# motor_control.net
KiCad netlist of a schematic drawn in EAGLE
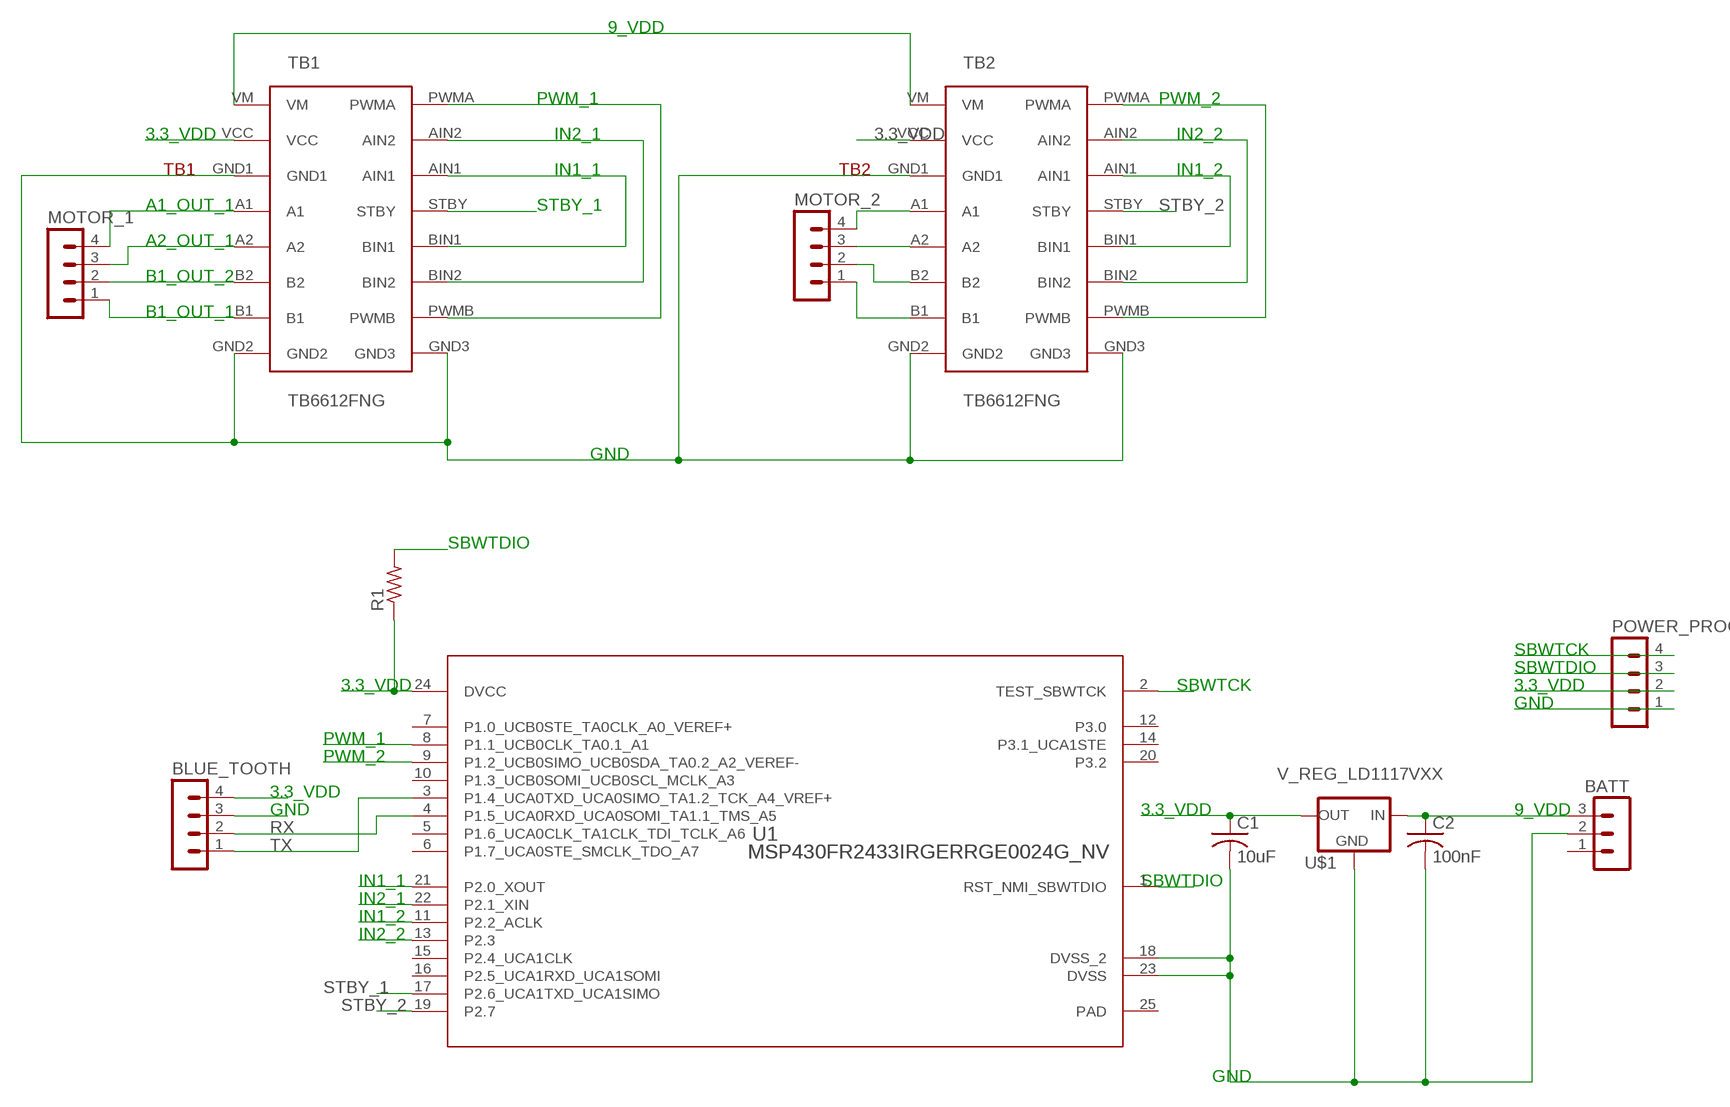
[diagram p0: schematic, sheet 1]

(export (version "E")
  (design (tool "Eeschema 10.0.6"))
  (components
    (comp (ref "BATT")
      (value "MA03-1")
      (footprint "eagle-import:MA03-1")
      (libsource (lib "eagle-import") (part "MA03-1"))
    )
    (comp (ref "BLUE_TOOTH")
      (value "MA04-1")
      (footprint "eagle-import:MA04-1")
      (libsource (lib "eagle-import") (part "MA04-1"))
    )
    (comp (ref "C1")
      (value "10uF")
      (footprint "eagle-import:C1206")
      (libsource (lib "eagle-import") (part "C-USC1206"))
    )
    (comp (ref "C2")
      (value "100nF")
      (footprint "eagle-import:C1206")
      (libsource (lib "eagle-import") (part "C-USC1206"))
    )
    (comp (ref "MOTOR_1")
      (value "MA04-1")
      (footprint "eagle-import:MA04-1")
      (libsource (lib "eagle-import") (part "MA04-1"))
    )
    (comp (ref "MOTOR_2")
      (value "MA04-1")
      (footprint "eagle-import:MA04-1")
      (libsource (lib "eagle-import") (part "MA04-1"))
    )
    (comp (ref "POWER_PROG")
      (value "MA04-1")
      (footprint "eagle-import:MA04-1")
      (libsource (lib "eagle-import") (part "MA04-1"))
    )
    (comp (ref "R1")
      (value "R-US_R1206")
      (footprint "eagle-import:R1206")
      (libsource (lib "eagle-import") (part "R-US_R1206"))
    )
    (comp (ref "TB1")
      (value "TB6612FNG")
      (footprint "eagle-import:TB6612FNG")
      (libsource (lib "eagle-import") (part "TB6612FNG"))
    )
    (comp (ref "TB2")
      (value "TB6612FNG")
      (footprint "eagle-import:TB6612FNG")
      (libsource (lib "eagle-import") (part "TB6612FNG"))
    )
    (comp (ref "U$1")
      (value "V_REG_LD1117VXX")
      (footprint "eagle-import:78XXL")
      (libsource (lib "eagle-import") (part "V_REG_LD1117VXX"))
    )
    (comp (ref "U1")
      (value "MSP430FR2433IRGERRGE0024G_NV")
      (footprint "eagle-import:RGE0024G_NV")
      (fields
        (field (name "MANUFACTURER_PART_NUMBER") "MSP430FR2433IRGER")
        (field (name "COPYRIGHT") "Copyright (C) 2023 Ultra Librarian. All rights reserved.")
      )
      (libsource (lib "eagle-import") (part "MSP430FR2433IRGERRGE0024G_NV"))
    )
  )
  (nets
    (net (code "1") (name "/3.3_VDD") (class "Default")
      (node (ref "BLUE_TOOTH") (pin "4") (pinfunction "4_4") (pintype "passive"))
      (node (ref "C1") (pin "1") (pinfunction "1_1") (pintype "passive"))
      (node (ref "POWER_PROG") (pin "2") (pinfunction "2_2") (pintype "passive"))
      (node (ref "R1") (pin "1") (pinfunction "1_1") (pintype "passive"))
      (node (ref "TB1") (pin "VCC") (pinfunction "VCC_VCC") (pintype "bidirectional"))
      (node (ref "TB2") (pin "VCC") (pinfunction "VCC_VCC") (pintype "bidirectional"))
      (node (ref "U$1") (pin "GND") (pinfunction "OUT_GND") (pintype "output"))
      (node (ref "U1") (pin "24") (pinfunction "DVCC_24") (pintype "power_in"))
    )
    (net (code "2") (name "/9_VDD") (class "Default")
      (node (ref "BATT") (pin "3") (pinfunction "3_3") (pintype "passive"))
      (node (ref "C2") (pin "1") (pinfunction "1_1") (pintype "passive"))
      (node (ref "TB1") (pin "VM") (pinfunction "VM_VM") (pintype "bidirectional"))
      (node (ref "TB2") (pin "VM") (pinfunction "VM_VM") (pintype "bidirectional"))
      (node (ref "U$1") (pin "OUT") (pinfunction "IN_OUT") (pintype "input"))
    )
    (net (code "3") (name "/A1_OUT_1") (class "Default")
      (node (ref "MOTOR_1") (pin "4") (pinfunction "4_4") (pintype "passive"))
      (node (ref "TB1") (pin "A1") (pinfunction "A1_A1") (pintype "bidirectional"))
    )
    (net (code "4") (name "/A2_OUT_1") (class "Default")
      (node (ref "MOTOR_1") (pin "3") (pinfunction "3_3") (pintype "passive"))
      (node (ref "TB1") (pin "A2") (pinfunction "A2_A2") (pintype "bidirectional"))
    )
    (net (code "5") (name "/B1_OUT_1") (class "Default")
      (node (ref "MOTOR_1") (pin "1") (pinfunction "1_1") (pintype "passive"))
      (node (ref "TB1") (pin "B1") (pinfunction "B1_B1") (pintype "bidirectional"))
    )
    (net (code "6") (name "/B1_OUT_2") (class "Default")
      (node (ref "MOTOR_1") (pin "2") (pinfunction "2_2") (pintype "passive"))
      (node (ref "TB1") (pin "B2") (pinfunction "B2_B2") (pintype "bidirectional"))
    )
    (net (code "7") (name "/GND") (class "Default")
      (node (ref "BATT") (pin "2") (pinfunction "2_2") (pintype "passive"))
      (node (ref "BLUE_TOOTH") (pin "3") (pinfunction "3_3") (pintype "passive"))
      (node (ref "C1") (pin "2") (pinfunction "2_2") (pintype "passive"))
      (node (ref "C2") (pin "2") (pinfunction "2_2") (pintype "passive"))
      (node (ref "POWER_PROG") (pin "1") (pinfunction "1_1") (pintype "passive"))
      (node (ref "TB1") (pin "GND1") (pinfunction "GND1_GND1") (pintype "bidirectional"))
      (node (ref "TB1") (pin "GND2") (pinfunction "GND2_GND2") (pintype "bidirectional"))
      (node (ref "TB1") (pin "GND3") (pinfunction "GND3_GND3") (pintype "bidirectional"))
      (node (ref "TB2") (pin "GND1") (pinfunction "GND1_GND1") (pintype "bidirectional"))
      (node (ref "TB2") (pin "GND2") (pinfunction "GND2_GND2") (pintype "bidirectional"))
      (node (ref "TB2") (pin "GND3") (pinfunction "GND3_GND3") (pintype "bidirectional"))
      (node (ref "U$1") (pin "IN") (pinfunction "GND_IN") (pintype "input"))
      (node (ref "U1") (pin "18") (pinfunction "DVSS_2_18") (pintype "power_in"))
      (node (ref "U1") (pin "23") (pinfunction "DVSS_23") (pintype "power_in"))
    )
    (net (code "8") (name "/IN1_1") (class "Default")
      (node (ref "TB1") (pin "AIN1") (pinfunction "AIN1_AIN1") (pintype "bidirectional"))
      (node (ref "TB1") (pin "BIN1") (pinfunction "BIN1_BIN1") (pintype "bidirectional"))
      (node (ref "U1") (pin "21") (pinfunction "P2.0_XOUT_21") (pintype "bidirectional"))
    )
    (net (code "9") (name "/IN1_2") (class "Default")
      (node (ref "TB2") (pin "AIN1") (pinfunction "AIN1_AIN1") (pintype "bidirectional"))
      (node (ref "TB2") (pin "BIN1") (pinfunction "BIN1_BIN1") (pintype "bidirectional"))
      (node (ref "U1") (pin "11") (pinfunction "P2.2_ACLK_11") (pintype "bidirectional"))
    )
    (net (code "10") (name "/IN2_1") (class "Default")
      (node (ref "TB1") (pin "AIN2") (pinfunction "AIN2_AIN2") (pintype "bidirectional"))
      (node (ref "TB1") (pin "BIN2") (pinfunction "BIN2_BIN2") (pintype "bidirectional"))
      (node (ref "U1") (pin "22") (pinfunction "P2.1_XIN_22") (pintype "bidirectional"))
    )
    (net (code "11") (name "/IN2_2") (class "Default")
      (node (ref "TB2") (pin "AIN2") (pinfunction "AIN2_AIN2") (pintype "bidirectional"))
      (node (ref "TB2") (pin "BIN2") (pinfunction "BIN2_BIN2") (pintype "bidirectional"))
      (node (ref "U1") (pin "13") (pinfunction "P2.3_13") (pintype "bidirectional"))
    )
    (net (code "12") (name "/PAD") (class "Default")
      (node (ref "U1") (pin "25") (pinfunction "PAD_25") (pintype "power_in"))
    )
    (net (code "13") (name "/PWM_1") (class "Default")
      (node (ref "TB1") (pin "PWMA") (pinfunction "PWMA_PWMA") (pintype "bidirectional"))
      (node (ref "TB1") (pin "PWMB") (pinfunction "PWMB_PWMB") (pintype "bidirectional"))
      (node (ref "U1") (pin "8") (pinfunction "P1.1_UCB0CLK_TA0.1_A1_8") (pintype "bidirectional"))
    )
    (net (code "14") (name "/PWM_2") (class "Default")
      (node (ref "TB2") (pin "PWMA") (pinfunction "PWMA_PWMA") (pintype "bidirectional"))
      (node (ref "TB2") (pin "PWMB") (pinfunction "PWMB_PWMB") (pintype "bidirectional"))
      (node (ref "U1") (pin "9") (pinfunction "P1.2_UCB0SIMO_UCB0SDA_TA0.2_A2_VEREF-_9") (pintype "bidirectional"))
    )
    (net (code "15") (name "/RX") (class "Default")
      (node (ref "BLUE_TOOTH") (pin "2") (pinfunction "2_2") (pintype "passive"))
      (node (ref "U1") (pin "4") (pinfunction "P1.5_UCA0RXD_UCA0SOMI_TA1.1_TMS_A5_4") (pintype "bidirectional"))
    )
    (net (code "16") (name "/SBWTCK") (class "Default")
      (node (ref "POWER_PROG") (pin "4") (pinfunction "4_4") (pintype "passive"))
      (node (ref "U1") (pin "2") (pinfunction "TEST_SBWTCK_2") (pintype "input"))
    )
    (net (code "17") (name "/SBWTDIO") (class "Default")
      (node (ref "POWER_PROG") (pin "3") (pinfunction "3_3") (pintype "passive"))
      (node (ref "R1") (pin "2") (pinfunction "2_2") (pintype "passive"))
      (node (ref "U1") (pin "1") (pinfunction "RST_NMI_SBWTDIO_1") (pintype "bidirectional"))
    )
    (net (code "18") (name "/STBY_1") (class "Default")
      (node (ref "TB1") (pin "STBY") (pinfunction "STBY_STBY") (pintype "bidirectional"))
      (node (ref "U1") (pin "17") (pinfunction "P2.6_UCA1TXD_UCA1SIMO_17") (pintype "bidirectional"))
    )
    (net (code "19") (name "/STBY_2") (class "Default")
      (node (ref "TB2") (pin "STBY") (pinfunction "STBY_STBY") (pintype "bidirectional"))
      (node (ref "U1") (pin "19") (pinfunction "P2.7_19") (pintype "bidirectional"))
    )
    (net (code "20") (name "/TX") (class "Default")
      (node (ref "BLUE_TOOTH") (pin "1") (pinfunction "1_1") (pintype "passive"))
      (node (ref "U1") (pin "3") (pinfunction "P1.4_UCA0TXD_UCA0SIMO_TA1.2_TCK_A4_VREF+_3") (pintype "bidirectional"))
    )
    (net (code "21") (name "Net-(MOTOR_2-Pad1)") (class "Default")
      (node (ref "MOTOR_2") (pin "1") (pinfunction "1_1") (pintype "passive"))
      (node (ref "TB2") (pin "B1") (pinfunction "B1_B1") (pintype "bidirectional"))
    )
    (net (code "22") (name "Net-(MOTOR_2-Pad2)") (class "Default")
      (node (ref "MOTOR_2") (pin "2") (pinfunction "2_2") (pintype "passive"))
      (node (ref "TB2") (pin "B2") (pinfunction "B2_B2") (pintype "bidirectional"))
    )
    (net (code "23") (name "Net-(MOTOR_2-Pad3)") (class "Default")
      (node (ref "MOTOR_2") (pin "3") (pinfunction "3_3") (pintype "passive"))
      (node (ref "TB2") (pin "A2") (pinfunction "A2_A2") (pintype "bidirectional"))
    )
    (net (code "24") (name "Net-(MOTOR_2-Pad4)") (class "Default")
      (node (ref "MOTOR_2") (pin "4") (pinfunction "4_4") (pintype "passive"))
      (node (ref "TB2") (pin "A1") (pinfunction "A1_A1") (pintype "bidirectional"))
    )
    (net (code "25") (name "unconnected-(BATT-Pad1)") (class "Default")
      (node (ref "BATT") (pin "1") (pinfunction "1_1") (pintype "passive"))
    )
    (net (code "26") (name "unconnected-(U1-P1.0_UCB0STE_TA0CLK_A0_VEREF+-Pad7)") (class "Default")
      (node (ref "U1") (pin "7") (pinfunction "P1.0_UCB0STE_TA0CLK_A0_VEREF+_7") (pintype "bidirectional"))
    )
    (net (code "27") (name "unconnected-(U1-P1.3_UCB0SOMI_UCB0SCL_MCLK_A3-Pad10)") (class "Default")
      (node (ref "U1") (pin "10") (pinfunction "P1.3_UCB0SOMI_UCB0SCL_MCLK_A3_10") (pintype "bidirectional"))
    )
    (net (code "28") (name "unconnected-(U1-P1.6_UCA0CLK_TA1CLK_TDI_TCLK_A6-Pad5)") (class "Default")
      (node (ref "U1") (pin "5") (pinfunction "P1.6_UCA0CLK_TA1CLK_TDI_TCLK_A6_5") (pintype "bidirectional"))
    )
    (net (code "29") (name "unconnected-(U1-P1.7_UCA0STE_SMCLK_TDO_A7-Pad6)") (class "Default")
      (node (ref "U1") (pin "6") (pinfunction "P1.7_UCA0STE_SMCLK_TDO_A7_6") (pintype "bidirectional"))
    )
    (net (code "30") (name "unconnected-(U1-P2.4_UCA1CLK-Pad15)") (class "Default")
      (node (ref "U1") (pin "15") (pinfunction "P2.4_UCA1CLK_15") (pintype "bidirectional"))
    )
    (net (code "31") (name "unconnected-(U1-P2.5_UCA1RXD_UCA1SOMI-Pad16)") (class "Default")
      (node (ref "U1") (pin "16") (pinfunction "P2.5_UCA1RXD_UCA1SOMI_16") (pintype "bidirectional"))
    )
    (net (code "32") (name "unconnected-(U1-P3.0-Pad12)") (class "Default")
      (node (ref "U1") (pin "12") (pinfunction "P3.0_12") (pintype "bidirectional"))
    )
    (net (code "33") (name "unconnected-(U1-P3.1_UCA1STE-Pad14)") (class "Default")
      (node (ref "U1") (pin "14") (pinfunction "P3.1_UCA1STE_14") (pintype "bidirectional"))
    )
    (net (code "34") (name "unconnected-(U1-P3.2-Pad20)") (class "Default")
      (node (ref "U1") (pin "20") (pinfunction "P3.2_20") (pintype "bidirectional"))
    )
  )
)
